# Sheet2.net
KiCad netlist of a schematic drawn in Altium Designer
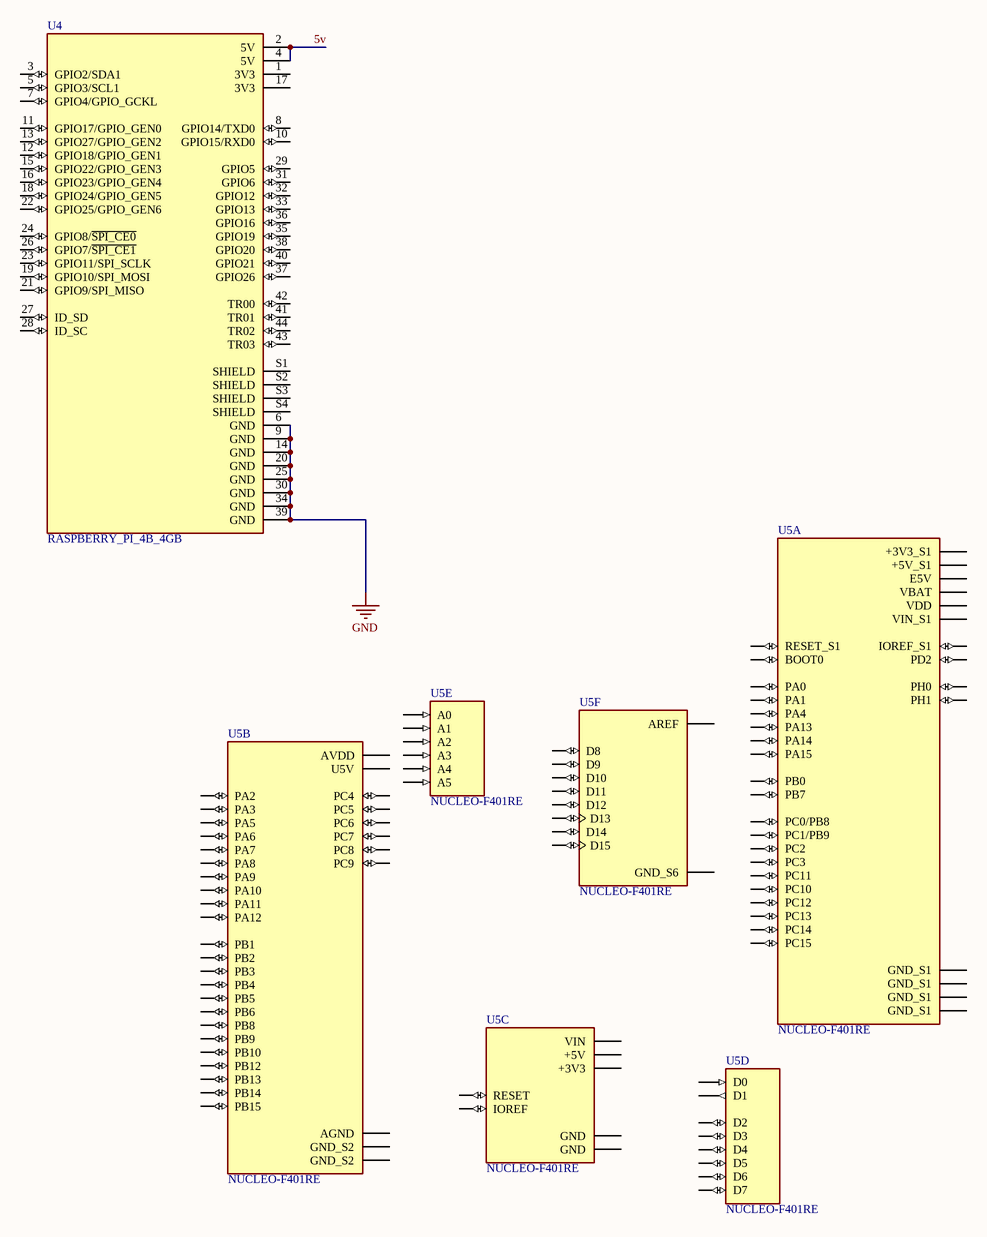
[diagram p0: Sheet2.SchDoc]

(export (version "E")
  (design (tool "Eeschema 10.0.6"))
  (components
    (comp (ref "U4")
      (value "RASPBERRY_PI_4B_4GB")
      (footprint "MODULE_RASPBERRY_PI_4B_4GB")
      (description "BCM2711 Raspberry Pi 4 Model B 4GB - ARMÂ® CortexÂ®-A72 MPU Embedded Evaluation Board")
      (fields (field (name "MF") "Raspberry Pi") (field (name "MP") "RASPBERRY PI 4B/4GB"))
      (libsource (lib "FH Graubünden") (part "RASPBERRY_PI_4B_4GB"))
    )
    (comp (ref "U5")
      (value "NUCLEO-F401RE")
      (footprint "ST_NUCLEO-F401RE")
      (libsource (lib "NUCLEO-F401RE") (part "NUCLEO-F401RE"))
    )
  )
  (nets
    (net (code "1") (name "/5v") (class "Default")
      (node (ref "U4") (pin "2") (pinfunction "5V_2") (pintype "power_in"))
      (node (ref "U4") (pin "4") (pinfunction "5V_4") (pintype "power_in"))
    )
    (net (code "2") (name "GND") (class "Default")
      (node (ref "U4") (pin "14") (pinfunction "GND_14") (pintype "power_in"))
      (node (ref "U4") (pin "20") (pinfunction "GND_20") (pintype "power_in"))
      (node (ref "U4") (pin "25") (pinfunction "GND_25") (pintype "power_in"))
      (node (ref "U4") (pin "30") (pinfunction "GND_30") (pintype "power_in"))
      (node (ref "U4") (pin "34") (pinfunction "GND_34") (pintype "power_in"))
      (node (ref "U4") (pin "39") (pinfunction "GND_39") (pintype "power_in"))
      (node (ref "U4") (pin "6") (pinfunction "GND_6") (pintype "power_in"))
      (node (ref "U4") (pin "9") (pinfunction "GND_9") (pintype "power_in"))
    )
    (net (code "3") (name "unconnected-(U4-3V3-Pad1)") (class "Default")
      (node (ref "U4") (pin "1") (pinfunction "3V3_1") (pintype "power_in"))
    )
    (net (code "4") (name "unconnected-(U4-3V3-Pad17)") (class "Default")
      (node (ref "U4") (pin "17") (pinfunction "3V3_17") (pintype "power_in"))
    )
    (net (code "5") (name "unconnected-(U4-GPIO2{slash}SDA1-Pad3)") (class "Default")
      (node (ref "U4") (pin "3") (pinfunction "GPIO2/SDA1_3") (pintype "bidirectional"))
    )
    (net (code "6") (name "unconnected-(U4-GPIO3{slash}SCL1-Pad5)") (class "Default")
      (node (ref "U4") (pin "5") (pinfunction "GPIO3/SCL1_5") (pintype "bidirectional"))
    )
    (net (code "7") (name "unconnected-(U4-GPIO4{slash}GPIO_GCKL-Pad7)") (class "Default")
      (node (ref "U4") (pin "7") (pinfunction "GPIO4/GPIO_GCKL_7") (pintype "bidirectional"))
    )
    (net (code "8") (name "unconnected-(U4-GPIO5-Pad29)") (class "Default")
      (node (ref "U4") (pin "29") (pinfunction "GPIO5_29") (pintype "bidirectional"))
    )
    (net (code "9") (name "unconnected-(U4-GPIO6-Pad31)") (class "Default")
      (node (ref "U4") (pin "31") (pinfunction "GPIO6_31") (pintype "bidirectional"))
    )
    (net (code "10") (name "unconnected-(U4-GPIO7{slash}~{SPI_CE1}-Pad26)") (class "Default")
      (node (ref "U4") (pin "26") (pinfunction "GPIO7/~{SPI_CE1}_26") (pintype "bidirectional"))
    )
    (net (code "11") (name "unconnected-(U4-GPIO8{slash}~{SPI_CE0}-Pad24)") (class "Default")
      (node (ref "U4") (pin "24") (pinfunction "GPIO8/~{SPI_CE0}_24") (pintype "bidirectional"))
    )
    (net (code "12") (name "unconnected-(U4-GPIO9{slash}SPI_MISO-Pad21)") (class "Default")
      (node (ref "U4") (pin "21") (pinfunction "GPIO9/SPI_MISO_21") (pintype "bidirectional"))
    )
    (net (code "13") (name "unconnected-(U4-GPIO10{slash}SPI_MOSI-Pad19)") (class "Default")
      (node (ref "U4") (pin "19") (pinfunction "GPIO10/SPI_MOSI_19") (pintype "bidirectional"))
    )
    (net (code "14") (name "unconnected-(U4-GPIO11{slash}SPI_SCLK-Pad23)") (class "Default")
      (node (ref "U4") (pin "23") (pinfunction "GPIO11/SPI_SCLK_23") (pintype "bidirectional"))
    )
    (net (code "15") (name "unconnected-(U4-GPIO12-Pad32)") (class "Default")
      (node (ref "U4") (pin "32") (pinfunction "GPIO12_32") (pintype "bidirectional"))
    )
    (net (code "16") (name "unconnected-(U4-GPIO13-Pad33)") (class "Default")
      (node (ref "U4") (pin "33") (pinfunction "GPIO13_33") (pintype "bidirectional"))
    )
    (net (code "17") (name "unconnected-(U4-GPIO14{slash}TXD0-Pad8)") (class "Default")
      (node (ref "U4") (pin "8") (pinfunction "GPIO14/TXD0_8") (pintype "bidirectional"))
    )
    (net (code "18") (name "unconnected-(U4-GPIO15{slash}RXD0-Pad10)") (class "Default")
      (node (ref "U4") (pin "10") (pinfunction "GPIO15/RXD0_10") (pintype "bidirectional"))
    )
    (net (code "19") (name "unconnected-(U4-GPIO16-Pad36)") (class "Default")
      (node (ref "U4") (pin "36") (pinfunction "GPIO16_36") (pintype "bidirectional"))
    )
    (net (code "20") (name "unconnected-(U4-GPIO17{slash}GPIO_GEN0-Pad11)") (class "Default")
      (node (ref "U4") (pin "11") (pinfunction "GPIO17/GPIO_GEN0_11") (pintype "bidirectional"))
    )
    (net (code "21") (name "unconnected-(U4-GPIO18{slash}GPIO_GEN1-Pad12)") (class "Default")
      (node (ref "U4") (pin "12") (pinfunction "GPIO18/GPIO_GEN1_12") (pintype "bidirectional"))
    )
    (net (code "22") (name "unconnected-(U4-GPIO19-Pad35)") (class "Default")
      (node (ref "U4") (pin "35") (pinfunction "GPIO19_35") (pintype "bidirectional"))
    )
    (net (code "23") (name "unconnected-(U4-GPIO20-Pad38)") (class "Default")
      (node (ref "U4") (pin "38") (pinfunction "GPIO20_38") (pintype "bidirectional"))
    )
    (net (code "24") (name "unconnected-(U4-GPIO21-Pad40)") (class "Default")
      (node (ref "U4") (pin "40") (pinfunction "GPIO21_40") (pintype "bidirectional"))
    )
    (net (code "25") (name "unconnected-(U4-GPIO22{slash}GPIO_GEN3-Pad15)") (class "Default")
      (node (ref "U4") (pin "15") (pinfunction "GPIO22/GPIO_GEN3_15") (pintype "bidirectional"))
    )
    (net (code "26") (name "unconnected-(U4-GPIO23{slash}GPIO_GEN4-Pad16)") (class "Default")
      (node (ref "U4") (pin "16") (pinfunction "GPIO23/GPIO_GEN4_16") (pintype "bidirectional"))
    )
    (net (code "27") (name "unconnected-(U4-GPIO24{slash}GPIO_GEN5-Pad18)") (class "Default")
      (node (ref "U4") (pin "18") (pinfunction "GPIO24/GPIO_GEN5_18") (pintype "bidirectional"))
    )
    (net (code "28") (name "unconnected-(U4-GPIO25{slash}GPIO_GEN6-Pad22)") (class "Default")
      (node (ref "U4") (pin "22") (pinfunction "GPIO25/GPIO_GEN6_22") (pintype "bidirectional"))
    )
    (net (code "29") (name "unconnected-(U4-GPIO26-Pad37)") (class "Default")
      (node (ref "U4") (pin "37") (pinfunction "GPIO26_37") (pintype "bidirectional"))
    )
    (net (code "30") (name "unconnected-(U4-GPIO27{slash}GPIO_GEN2-Pad13)") (class "Default")
      (node (ref "U4") (pin "13") (pinfunction "GPIO27/GPIO_GEN2_13") (pintype "bidirectional"))
    )
    (net (code "31") (name "unconnected-(U4-ID_SC-Pad28)") (class "Default")
      (node (ref "U4") (pin "28") (pinfunction "ID_SC_28") (pintype "bidirectional"))
    )
    (net (code "32") (name "unconnected-(U4-ID_SD-Pad27)") (class "Default")
      (node (ref "U4") (pin "27") (pinfunction "ID_SD_27") (pintype "bidirectional"))
    )
    (net (code "33") (name "unconnected-(U4-SHIELD-PadS1)") (class "Default")
      (node (ref "U4") (pin "S1") (pinfunction "SHIELD_S1") (pintype "power_in"))
    )
    (net (code "34") (name "unconnected-(U4-SHIELD-PadS2)") (class "Default")
      (node (ref "U4") (pin "S2") (pinfunction "SHIELD_S2") (pintype "power_in"))
    )
    (net (code "35") (name "unconnected-(U4-SHIELD-PadS3)") (class "Default")
      (node (ref "U4") (pin "S3") (pinfunction "SHIELD_S3") (pintype "power_in"))
    )
    (net (code "36") (name "unconnected-(U4-SHIELD-PadS4)") (class "Default")
      (node (ref "U4") (pin "S4") (pinfunction "SHIELD_S4") (pintype "power_in"))
    )
    (net (code "37") (name "unconnected-(U4-TR00-Pad42)") (class "Default")
      (node (ref "U4") (pin "42") (pinfunction "TR00_42") (pintype "bidirectional"))
    )
    (net (code "38") (name "unconnected-(U4-TR01-Pad41)") (class "Default")
      (node (ref "U4") (pin "41") (pinfunction "TR01_41") (pintype "bidirectional"))
    )
    (net (code "39") (name "unconnected-(U4-TR02-Pad44)") (class "Default")
      (node (ref "U4") (pin "44") (pinfunction "TR02_44") (pintype "bidirectional"))
    )
    (net (code "40") (name "unconnected-(U4-TR03-Pad43)") (class "Default")
      (node (ref "U4") (pin "43") (pinfunction "TR03_43") (pintype "bidirectional"))
    )
    (net (code "41") (name "unconnected-(U5A-+3V3_S1-PadCN7_16)") (class "Default")
      (node (ref "U5") (pin "CN7_16") (pinfunction "+3V3_S1_CN7_16") (pintype "power_in"))
    )
    (net (code "42") (name "unconnected-(U5A-+5V_S1-PadCN7_18)") (class "Default")
      (node (ref "U5") (pin "CN7_18") (pinfunction "+5V_S1_CN7_18") (pintype "power_in"))
    )
    (net (code "43") (name "unconnected-(U5A-BOOT0-PadCN7_7)") (class "Default")
      (node (ref "U5") (pin "CN7_7") (pinfunction "BOOT0_CN7_7") (pintype "bidirectional"))
    )
    (net (code "44") (name "unconnected-(U5A-E5V-PadCN7_6)") (class "Default")
      (node (ref "U5") (pin "CN7_6") (pinfunction "E5V_CN7_6") (pintype "power_in"))
    )
    (net (code "45") (name "unconnected-(U5A-GND_S1-PadCN7_8)") (class "Default")
      (node (ref "U5") (pin "CN7_8") (pinfunction "GND_S1_CN7_8") (pintype "power_in"))
    )
    (net (code "46") (name "unconnected-(U5A-GND_S1-PadCN7_19)") (class "Default")
      (node (ref "U5") (pin "CN7_19") (pinfunction "GND_S1_CN7_19") (pintype "power_in"))
    )
    (net (code "47") (name "unconnected-(U5A-GND_S1-PadCN7_20)") (class "Default")
      (node (ref "U5") (pin "CN7_20") (pinfunction "GND_S1_CN7_20") (pintype "power_in"))
    )
    (net (code "48") (name "unconnected-(U5A-GND_S1-PadCN7_22)") (class "Default")
      (node (ref "U5") (pin "CN7_22") (pinfunction "GND_S1_CN7_22") (pintype "power_in"))
    )
    (net (code "49") (name "unconnected-(U5A-IOREF_S1-PadCN7_12)") (class "Default")
      (node (ref "U5") (pin "CN7_12") (pinfunction "IOREF_S1_CN7_12") (pintype "bidirectional"))
    )
    (net (code "50") (name "unconnected-(U5A-PA0-PadCN7_28)") (class "Default")
      (node (ref "U5") (pin "CN7_28") (pinfunction "PA0_CN7_28") (pintype "bidirectional"))
    )
    (net (code "51") (name "unconnected-(U5A-PA1-PadCN7_30)") (class "Default")
      (node (ref "U5") (pin "CN7_30") (pinfunction "PA1_CN7_30") (pintype "bidirectional"))
    )
    (net (code "52") (name "unconnected-(U5A-PA4-PadCN7_32)") (class "Default")
      (node (ref "U5") (pin "CN7_32") (pinfunction "PA4_CN7_32") (pintype "bidirectional"))
    )
    (net (code "53") (name "unconnected-(U5A-PA13-PadCN7_13)") (class "Default")
      (node (ref "U5") (pin "CN7_13") (pinfunction "PA13_CN7_13") (pintype "bidirectional"))
    )
    (net (code "54") (name "unconnected-(U5A-PA14-PadCN7_15)") (class "Default")
      (node (ref "U5") (pin "CN7_15") (pinfunction "PA14_CN7_15") (pintype "bidirectional"))
    )
    (net (code "55") (name "unconnected-(U5A-PA15-PadCN7_17)") (class "Default")
      (node (ref "U5") (pin "CN7_17") (pinfunction "PA15_CN7_17") (pintype "bidirectional"))
    )
    (net (code "56") (name "unconnected-(U5A-PB0-PadCN7_34)") (class "Default")
      (node (ref "U5") (pin "CN7_34") (pinfunction "PB0_CN7_34") (pintype "bidirectional"))
    )
    (net (code "57") (name "unconnected-(U5A-PB7-PadCN7_21)") (class "Default")
      (node (ref "U5") (pin "CN7_21") (pinfunction "PB7_CN7_21") (pintype "bidirectional"))
    )
    (net (code "58") (name "unconnected-(U5A-PC0{slash}PB8-PadCN7_38)") (class "Default")
      (node (ref "U5") (pin "CN7_38") (pinfunction "PC0/PB8_CN7_38") (pintype "bidirectional"))
    )
    (net (code "59") (name "unconnected-(U5A-PC1{slash}PB9-PadCN7_36)") (class "Default")
      (node (ref "U5") (pin "CN7_36") (pinfunction "PC1/PB9_CN7_36") (pintype "bidirectional"))
    )
    (net (code "60") (name "unconnected-(U5A-PC2-PadCN7_35)") (class "Default")
      (node (ref "U5") (pin "CN7_35") (pinfunction "PC2_CN7_35") (pintype "bidirectional"))
    )
    (net (code "61") (name "unconnected-(U5A-PC3-PadCN7_37)") (class "Default")
      (node (ref "U5") (pin "CN7_37") (pinfunction "PC3_CN7_37") (pintype "bidirectional"))
    )
    (net (code "62") (name "unconnected-(U5A-PC10-PadCN7_1)") (class "Default")
      (node (ref "U5") (pin "CN7_1") (pinfunction "PC10_CN7_1") (pintype "bidirectional"))
    )
    (net (code "63") (name "unconnected-(U5A-PC11-PadCN7_2)") (class "Default")
      (node (ref "U5") (pin "CN7_2") (pinfunction "PC11_CN7_2") (pintype "bidirectional"))
    )
    (net (code "64") (name "unconnected-(U5A-PC12-PadCN7_3)") (class "Default")
      (node (ref "U5") (pin "CN7_3") (pinfunction "PC12_CN7_3") (pintype "bidirectional"))
    )
    (net (code "65") (name "unconnected-(U5A-PC13-PadCN7_23)") (class "Default")
      (node (ref "U5") (pin "CN7_23") (pinfunction "PC13_CN7_23") (pintype "bidirectional"))
    )
    (net (code "66") (name "unconnected-(U5A-PC14-PadCN7_25)") (class "Default")
      (node (ref "U5") (pin "CN7_25") (pinfunction "PC14_CN7_25") (pintype "bidirectional"))
    )
    (net (code "67") (name "unconnected-(U5A-PC15-PadCN7_27)") (class "Default")
      (node (ref "U5") (pin "CN7_27") (pinfunction "PC15_CN7_27") (pintype "bidirectional"))
    )
    (net (code "68") (name "unconnected-(U5A-PD2-PadCN7_4)") (class "Default")
      (node (ref "U5") (pin "CN7_4") (pinfunction "PD2_CN7_4") (pintype "bidirectional"))
    )
    (net (code "69") (name "unconnected-(U5A-PH0-PadCN7_29)") (class "Default")
      (node (ref "U5") (pin "CN7_29") (pinfunction "PH0_CN7_29") (pintype "bidirectional"))
    )
    (net (code "70") (name "unconnected-(U5A-PH1-PadCN7_31)") (class "Default")
      (node (ref "U5") (pin "CN7_31") (pinfunction "PH1_CN7_31") (pintype "bidirectional"))
    )
    (net (code "71") (name "unconnected-(U5A-RESET_S1-PadCN7_14)") (class "Default")
      (node (ref "U5") (pin "CN7_14") (pinfunction "RESET_S1_CN7_14") (pintype "bidirectional"))
    )
    (net (code "72") (name "unconnected-(U5A-VBAT-PadCN7_33)") (class "Default")
      (node (ref "U5") (pin "CN7_33") (pinfunction "VBAT_CN7_33") (pintype "power_in"))
    )
    (net (code "73") (name "unconnected-(U5A-VDD-PadCN7_5)") (class "Default")
      (node (ref "U5") (pin "CN7_5") (pinfunction "VDD_CN7_5") (pintype "power_in"))
    )
    (net (code "74") (name "unconnected-(U5A-VIN_S1-PadCN7_24)") (class "Default")
      (node (ref "U5") (pin "CN7_24") (pinfunction "VIN_S1_CN7_24") (pintype "power_in"))
    )
    (net (code "75") (name "unconnected-(U5B-AGND-PadCN10_32)") (class "Default")
      (node (ref "U5") (pin "CN10_32") (pinfunction "AGND_CN10_32") (pintype "power_in"))
    )
    (net (code "76") (name "unconnected-(U5B-AVDD-PadCN10_7)") (class "Default")
      (node (ref "U5") (pin "CN10_7") (pinfunction "AVDD_CN10_7") (pintype "power_in"))
    )
    (net (code "77") (name "unconnected-(U5B-GND_S2-PadCN10_9)") (class "Default")
      (node (ref "U5") (pin "CN10_9") (pinfunction "GND_S2_CN10_9") (pintype "power_in"))
    )
    (net (code "78") (name "unconnected-(U5B-GND_S2-PadCN10_20)") (class "Default")
      (node (ref "U5") (pin "CN10_20") (pinfunction "GND_S2_CN10_20") (pintype "power_in"))
    )
    (net (code "79") (name "unconnected-(U5B-PA2-PadCN10_35)") (class "Default")
      (node (ref "U5") (pin "CN10_35") (pinfunction "PA2_CN10_35") (pintype "bidirectional"))
    )
    (net (code "80") (name "unconnected-(U5B-PA3-PadCN10_37)") (class "Default")
      (node (ref "U5") (pin "CN10_37") (pinfunction "PA3_CN10_37") (pintype "bidirectional"))
    )
    (net (code "81") (name "unconnected-(U5B-PA5-PadCN10_11)") (class "Default")
      (node (ref "U5") (pin "CN10_11") (pinfunction "PA5_CN10_11") (pintype "bidirectional"))
    )
    (net (code "82") (name "unconnected-(U5B-PA6-PadCN10_13)") (class "Default")
      (node (ref "U5") (pin "CN10_13") (pinfunction "PA6_CN10_13") (pintype "bidirectional"))
    )
    (net (code "83") (name "unconnected-(U5B-PA7-PadCN10_15)") (class "Default")
      (node (ref "U5") (pin "CN10_15") (pinfunction "PA7_CN10_15") (pintype "bidirectional"))
    )
    (net (code "84") (name "unconnected-(U5B-PA8-PadCN10_23)") (class "Default")
      (node (ref "U5") (pin "CN10_23") (pinfunction "PA8_CN10_23") (pintype "bidirectional"))
    )
    (net (code "85") (name "unconnected-(U5B-PA9-PadCN10_21)") (class "Default")
      (node (ref "U5") (pin "CN10_21") (pinfunction "PA9_CN10_21") (pintype "bidirectional"))
    )
    (net (code "86") (name "unconnected-(U5B-PA10-PadCN10_33)") (class "Default")
      (node (ref "U5") (pin "CN10_33") (pinfunction "PA10_CN10_33") (pintype "bidirectional"))
    )
    (net (code "87") (name "unconnected-(U5B-PA11-PadCN10_14)") (class "Default")
      (node (ref "U5") (pin "CN10_14") (pinfunction "PA11_CN10_14") (pintype "bidirectional"))
    )
    (net (code "88") (name "unconnected-(U5B-PA12-PadCN10_12)") (class "Default")
      (node (ref "U5") (pin "CN10_12") (pinfunction "PA12_CN10_12") (pintype "bidirectional"))
    )
    (net (code "89") (name "unconnected-(U5B-PB1-PadCN10_24)") (class "Default")
      (node (ref "U5") (pin "CN10_24") (pinfunction "PB1_CN10_24") (pintype "bidirectional"))
    )
    (net (code "90") (name "unconnected-(U5B-PB2-PadCN10_22)") (class "Default")
      (node (ref "U5") (pin "CN10_22") (pinfunction "PB2_CN10_22") (pintype "bidirectional"))
    )
    (net (code "91") (name "unconnected-(U5B-PB3-PadCN10_31)") (class "Default")
      (node (ref "U5") (pin "CN10_31") (pinfunction "PB3_CN10_31") (pintype "bidirectional"))
    )
    (net (code "92") (name "unconnected-(U5B-PB4-PadCN10_27)") (class "Default")
      (node (ref "U5") (pin "CN10_27") (pinfunction "PB4_CN10_27") (pintype "bidirectional"))
    )
    (net (code "93") (name "unconnected-(U5B-PB5-PadCN10_29)") (class "Default")
      (node (ref "U5") (pin "CN10_29") (pinfunction "PB5_CN10_29") (pintype "bidirectional"))
    )
    (net (code "94") (name "unconnected-(U5B-PB6-PadCN10_17)") (class "Default")
      (node (ref "U5") (pin "CN10_17") (pinfunction "PB6_CN10_17") (pintype "bidirectional"))
    )
    (net (code "95") (name "unconnected-(U5B-PB8-PadCN10_3)") (class "Default")
      (node (ref "U5") (pin "CN10_3") (pinfunction "PB8_CN10_3") (pintype "bidirectional"))
    )
    (net (code "96") (name "unconnected-(U5B-PB9-PadCN10_5)") (class "Default")
      (node (ref "U5") (pin "CN10_5") (pinfunction "PB9_CN10_5") (pintype "bidirectional"))
    )
    (net (code "97") (name "unconnected-(U5B-PB10-PadCN10_25)") (class "Default")
      (node (ref "U5") (pin "CN10_25") (pinfunction "PB10_CN10_25") (pintype "bidirectional"))
    )
    (net (code "98") (name "unconnected-(U5B-PB12-PadCN10_16)") (class "Default")
      (node (ref "U5") (pin "CN10_16") (pinfunction "PB12_CN10_16") (pintype "bidirectional"))
    )
    (net (code "99") (name "unconnected-(U5B-PB13-PadCN10_30)") (class "Default")
      (node (ref "U5") (pin "CN10_30") (pinfunction "PB13_CN10_30") (pintype "bidirectional"))
    )
    (net (code "100") (name "unconnected-(U5B-PB14-PadCN10_28)") (class "Default")
      (node (ref "U5") (pin "CN10_28") (pinfunction "PB14_CN10_28") (pintype "bidirectional"))
    )
    (net (code "101") (name "unconnected-(U5B-PB15-PadCN10_26)") (class "Default")
      (node (ref "U5") (pin "CN10_26") (pinfunction "PB15_CN10_26") (pintype "bidirectional"))
    )
    (net (code "102") (name "unconnected-(U5B-PC4-PadCN10_34)") (class "Default")
      (node (ref "U5") (pin "CN10_34") (pinfunction "PC4_CN10_34") (pintype "bidirectional"))
    )
    (net (code "103") (name "unconnected-(U5B-PC5-PadCN10_6)") (class "Default")
      (node (ref "U5") (pin "CN10_6") (pinfunction "PC5_CN10_6") (pintype "bidirectional"))
    )
    (net (code "104") (name "unconnected-(U5B-PC6-PadCN10_4)") (class "Default")
      (node (ref "U5") (pin "CN10_4") (pinfunction "PC6_CN10_4") (pintype "bidirectional"))
    )
    (net (code "105") (name "unconnected-(U5B-PC7-PadCN10_19)") (class "Default")
      (node (ref "U5") (pin "CN10_19") (pinfunction "PC7_CN10_19") (pintype "bidirectional"))
    )
    (net (code "106") (name "unconnected-(U5B-PC8-PadCN10_2)") (class "Default")
      (node (ref "U5") (pin "CN10_2") (pinfunction "PC8_CN10_2") (pintype "bidirectional"))
    )
    (net (code "107") (name "unconnected-(U5B-PC9-PadCN10_1)") (class "Default")
      (node (ref "U5") (pin "CN10_1") (pinfunction "PC9_CN10_1") (pintype "bidirectional"))
    )
    (net (code "108") (name "unconnected-(U5B-U5V-PadCN10_8)") (class "Default")
      (node (ref "U5") (pin "CN10_8") (pinfunction "U5V_CN10_8") (pintype "power_in"))
    )
    (net (code "109") (name "unconnected-(U5C-+3V3-PadCN6_4)") (class "Default")
      (node (ref "U5") (pin "CN6_4") (pinfunction "+3V3_CN6_4") (pintype "power_in"))
    )
    (net (code "110") (name "unconnected-(U5C-+5V-PadCN6_5)") (class "Default")
      (node (ref "U5") (pin "CN6_5") (pinfunction "+5V_CN6_5") (pintype "power_in"))
    )
    (net (code "111") (name "unconnected-(U5C-GND-PadCN6_6)") (class "Default")
      (node (ref "U5") (pin "CN6_6") (pinfunction "GND_CN6_6") (pintype "power_in"))
    )
    (net (code "112") (name "unconnected-(U5C-GND-PadCN6_7)") (class "Default")
      (node (ref "U5") (pin "CN6_7") (pinfunction "GND_CN6_7") (pintype "power_in"))
    )
    (net (code "113") (name "unconnected-(U5C-IOREF-PadCN6_2)") (class "Default")
      (node (ref "U5") (pin "CN6_2") (pinfunction "IOREF_CN6_2") (pintype "bidirectional"))
    )
    (net (code "114") (name "unconnected-(U5C-RESET-PadCN6_3)") (class "Default")
      (node (ref "U5") (pin "CN6_3") (pinfunction "RESET_CN6_3") (pintype "bidirectional"))
    )
    (net (code "115") (name "unconnected-(U5C-VIN-PadCN6_8)") (class "Default")
      (node (ref "U5") (pin "CN6_8") (pinfunction "VIN_CN6_8") (pintype "power_in"))
    )
    (net (code "116") (name "unconnected-(U5D-D0-PadCN9_1)") (class "Default")
      (node (ref "U5") (pin "CN9_1") (pinfunction "D0_CN9_1") (pintype "input"))
    )
    (net (code "117") (name "unconnected-(U5D-D1-PadCN9_2)") (class "Default")
      (node (ref "U5") (pin "CN9_2") (pinfunction "D1_CN9_2") (pintype "output"))
    )
    (net (code "118") (name "unconnected-(U5D-D2-PadCN9_3)") (class "Default")
      (node (ref "U5") (pin "CN9_3") (pinfunction "D2_CN9_3") (pintype "bidirectional"))
    )
    (net (code "119") (name "unconnected-(U5D-D3-PadCN9_4)") (class "Default")
      (node (ref "U5") (pin "CN9_4") (pinfunction "D3_CN9_4") (pintype "bidirectional"))
    )
    (net (code "120") (name "unconnected-(U5D-D4-PadCN9_5)") (class "Default")
      (node (ref "U5") (pin "CN9_5") (pinfunction "D4_CN9_5") (pintype "bidirectional"))
    )
    (net (code "121") (name "unconnected-(U5D-D5-PadCN9_6)") (class "Default")
      (node (ref "U5") (pin "CN9_6") (pinfunction "D5_CN9_6") (pintype "bidirectional"))
    )
    (net (code "122") (name "unconnected-(U5D-D6-PadCN9_7)") (class "Default")
      (node (ref "U5") (pin "CN9_7") (pinfunction "D6_CN9_7") (pintype "bidirectional"))
    )
    (net (code "123") (name "unconnected-(U5D-D7-PadCN9_8)") (class "Default")
      (node (ref "U5") (pin "CN9_8") (pinfunction "D7_CN9_8") (pintype "bidirectional"))
    )
    (net (code "124") (name "unconnected-(U5E-A0-PadCN8_1)") (class "Default")
      (node (ref "U5") (pin "CN8_1") (pinfunction "A0_CN8_1") (pintype "input"))
    )
    (net (code "125") (name "unconnected-(U5E-A1-PadCN8_2)") (class "Default")
      (node (ref "U5") (pin "CN8_2") (pinfunction "A1_CN8_2") (pintype "input"))
    )
    (net (code "126") (name "unconnected-(U5E-A2-PadCN8_3)") (class "Default")
      (node (ref "U5") (pin "CN8_3") (pinfunction "A2_CN8_3") (pintype "input"))
    )
    (net (code "127") (name "unconnected-(U5E-A3-PadCN8_4)") (class "Default")
      (node (ref "U5") (pin "CN8_4") (pinfunction "A3_CN8_4") (pintype "input"))
    )
    (net (code "128") (name "unconnected-(U5E-A4-PadCN8_5)") (class "Default")
      (node (ref "U5") (pin "CN8_5") (pinfunction "A4_CN8_5") (pintype "input"))
    )
    (net (code "129") (name "unconnected-(U5E-A5-PadCN8_6)") (class "Default")
      (node (ref "U5") (pin "CN8_6") (pinfunction "A5_CN8_6") (pintype "input"))
    )
    (net (code "130") (name "unconnected-(U5F-AREF-PadCN5_8)") (class "Default")
      (node (ref "U5") (pin "CN5_8") (pinfunction "AREF_CN5_8") (pintype "power_in"))
    )
    (net (code "131") (name "unconnected-(U5F-D8-PadCN5_1)") (class "Default")
      (node (ref "U5") (pin "CN5_1") (pinfunction "D8_CN5_1") (pintype "bidirectional"))
    )
    (net (code "132") (name "unconnected-(U5F-D9-PadCN5_2)") (class "Default")
      (node (ref "U5") (pin "CN5_2") (pinfunction "D9_CN5_2") (pintype "bidirectional"))
    )
    (net (code "133") (name "unconnected-(U5F-D10-PadCN5_3)") (class "Default")
      (node (ref "U5") (pin "CN5_3") (pinfunction "D10_CN5_3") (pintype "bidirectional"))
    )
    (net (code "134") (name "unconnected-(U5F-D11-PadCN5_4)") (class "Default")
      (node (ref "U5") (pin "CN5_4") (pinfunction "D11_CN5_4") (pintype "bidirectional"))
    )
    (net (code "135") (name "unconnected-(U5F-D12-PadCN5_5)") (class "Default")
      (node (ref "U5") (pin "CN5_5") (pinfunction "D12_CN5_5") (pintype "bidirectional"))
    )
    (net (code "136") (name "unconnected-(U5F-D13-PadCN5_6)") (class "Default")
      (node (ref "U5") (pin "CN5_6") (pinfunction "D13_CN5_6") (pintype "bidirectional"))
    )
    (net (code "137") (name "unconnected-(U5F-D14-PadCN5_9)") (class "Default")
      (node (ref "U5") (pin "CN5_9") (pinfunction "D14_CN5_9") (pintype "bidirectional"))
    )
    (net (code "138") (name "unconnected-(U5F-D15-PadCN5_10)") (class "Default")
      (node (ref "U5") (pin "CN5_10") (pinfunction "D15_CN5_10") (pintype "bidirectional"))
    )
    (net (code "139") (name "unconnected-(U5F-GND_S6-PadCN5_7)") (class "Default")
      (node (ref "U5") (pin "CN5_7") (pinfunction "GND_S6_CN5_7") (pintype "power_in"))
    )
  )
)
